# AS1322.net
KiCad netlist of a schematic drawn in EAGLE
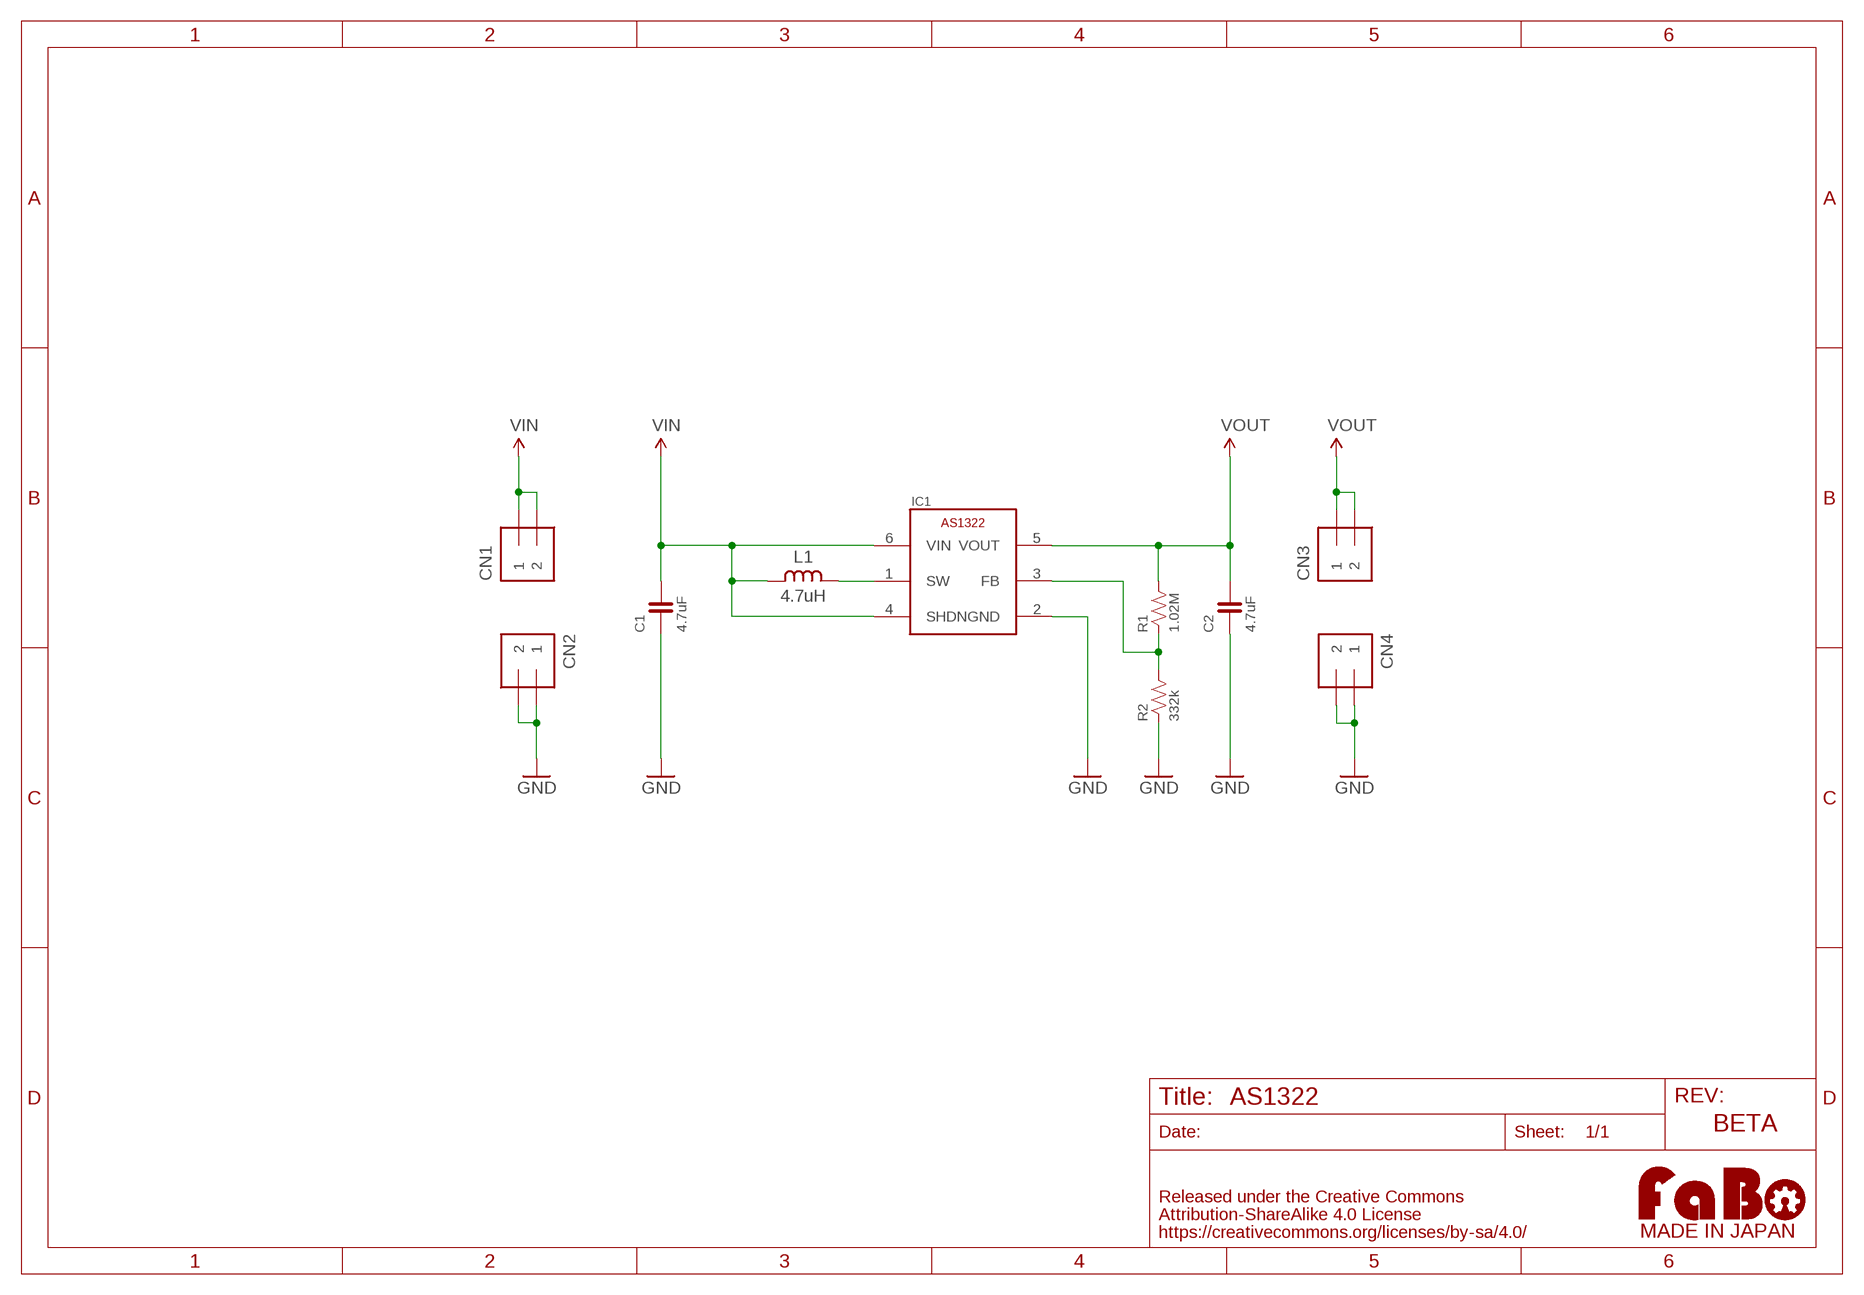
[diagram p0: schematic, sheet 1]

(export (version "E")
  (design (tool "Eeschema 10.0.6"))
  (components
    (comp (ref "C1")
      (value "4.7uF")
      (footprint "eagle-import:0603-NARROW")
      (libsource (lib "eagle-import") (part "CAPACITOR-0603_NARROW"))
    )
    (comp (ref "C2")
      (value "4.7uF")
      (footprint "eagle-import:0603-NARROW")
      (libsource (lib "eagle-import") (part "CAPACITOR-0603_NARROW"))
    )
    (comp (ref "CN1")
      (value "PIN_HEADER_1X2")
      (footprint "eagle-import:PIN_1X2")
      (libsource (lib "eagle-import") (part "PIN_HEADER_1X2"))
    )
    (comp (ref "CN2")
      (value "PIN_HEADER_1X2")
      (footprint "eagle-import:PIN_1X2")
      (libsource (lib "eagle-import") (part "PIN_HEADER_1X2"))
    )
    (comp (ref "CN3")
      (value "PIN_HEADER_1X2")
      (footprint "eagle-import:PIN_1X2")
      (libsource (lib "eagle-import") (part "PIN_HEADER_1X2"))
    )
    (comp (ref "CN4")
      (value "PIN_HEADER_1X2")
      (footprint "eagle-import:PIN_1X2")
      (libsource (lib "eagle-import") (part "PIN_HEADER_1X2"))
    )
    (comp (ref "IC1")
      (value "AS1322")
      (footprint "eagle-import:TSOT-23-6")
      (libsource (lib "eagle-import") (part "AS1322"))
    )
    (comp (ref "L1")
      (value "4.7uH")
      (footprint "eagle-import:LQH3NPN")
      (libsource (lib "eagle-import") (part "INDUCTOR-LQH3NPN"))
    )
    (comp (ref "R1")
      (value "1.02M")
      (footprint "eagle-import:0603-NARROW")
      (libsource (lib "eagle-import") (part "RESISTOR-0603-NARROW"))
    )
    (comp (ref "R2")
      (value "332k")
      (footprint "eagle-import:0603-NARROW")
      (libsource (lib "eagle-import") (part "RESISTOR-0603-NARROW"))
    )
    (comp (ref "U$2")
      (value "LOGO_FABO-M_BOTTOM")
      (footprint "eagle-import:LOGO_FABO_MS_BOTTOM")
      (libsource (lib "eagle-import") (part "LOGO_FABO-M_BOTTOM"))
    )
  )
  (nets
    (net (code "1") (name "GND") (class "Default")
      (node (ref "C1") (pin "1") (pinfunction "1_1") (pintype "passive"))
      (node (ref "C2") (pin "1") (pinfunction "1_1") (pintype "passive"))
      (node (ref "CN2") (pin "1") (pinfunction "1_1") (pintype "bidirectional"))
      (node (ref "CN2") (pin "2") (pinfunction "2_2") (pintype "bidirectional"))
      (node (ref "CN4") (pin "1") (pinfunction "1_1") (pintype "bidirectional"))
      (node (ref "CN4") (pin "2") (pinfunction "2_2") (pintype "bidirectional"))
      (node (ref "IC1") (pin "2") (pinfunction "GND_2") (pintype "bidirectional"))
      (node (ref "R2") (pin "1") (pinfunction "1_1") (pintype "bidirectional"))
    )
    (net (code "2") (name "Net-(IC1-FB)") (class "Default")
      (node (ref "IC1") (pin "3") (pinfunction "FB_3") (pintype "bidirectional"))
      (node (ref "R1") (pin "1") (pinfunction "1_1") (pintype "bidirectional"))
      (node (ref "R2") (pin "2") (pinfunction "2_2") (pintype "bidirectional"))
    )
    (net (code "3") (name "Net-(IC1-SW)") (class "Default")
      (node (ref "IC1") (pin "1") (pinfunction "SW_1") (pintype "bidirectional"))
      (node (ref "L1") (pin "2") (pinfunction "2_2") (pintype "bidirectional"))
    )
    (net (code "4") (name "VIN") (class "Default")
      (node (ref "C1") (pin "2") (pinfunction "2_2") (pintype "passive"))
      (node (ref "CN1") (pin "1") (pinfunction "1_1") (pintype "bidirectional"))
      (node (ref "CN1") (pin "2") (pinfunction "2_2") (pintype "bidirectional"))
      (node (ref "IC1") (pin "4") (pinfunction "SHDN_4") (pintype "bidirectional"))
      (node (ref "IC1") (pin "6") (pinfunction "VIN_6") (pintype "bidirectional"))
      (node (ref "L1") (pin "1") (pinfunction "1_1") (pintype "bidirectional"))
    )
    (net (code "5") (name "VOUT") (class "Default")
      (node (ref "C2") (pin "2") (pinfunction "2_2") (pintype "passive"))
      (node (ref "CN3") (pin "1") (pinfunction "1_1") (pintype "bidirectional"))
      (node (ref "CN3") (pin "2") (pinfunction "2_2") (pintype "bidirectional"))
      (node (ref "IC1") (pin "5") (pinfunction "VOUT_5") (pintype "bidirectional"))
      (node (ref "R1") (pin "2") (pinfunction "2_2") (pintype "bidirectional"))
    )
  )
)
